# Front_LDR.net
KiCad netlist of a schematic drawn in Altium Designer
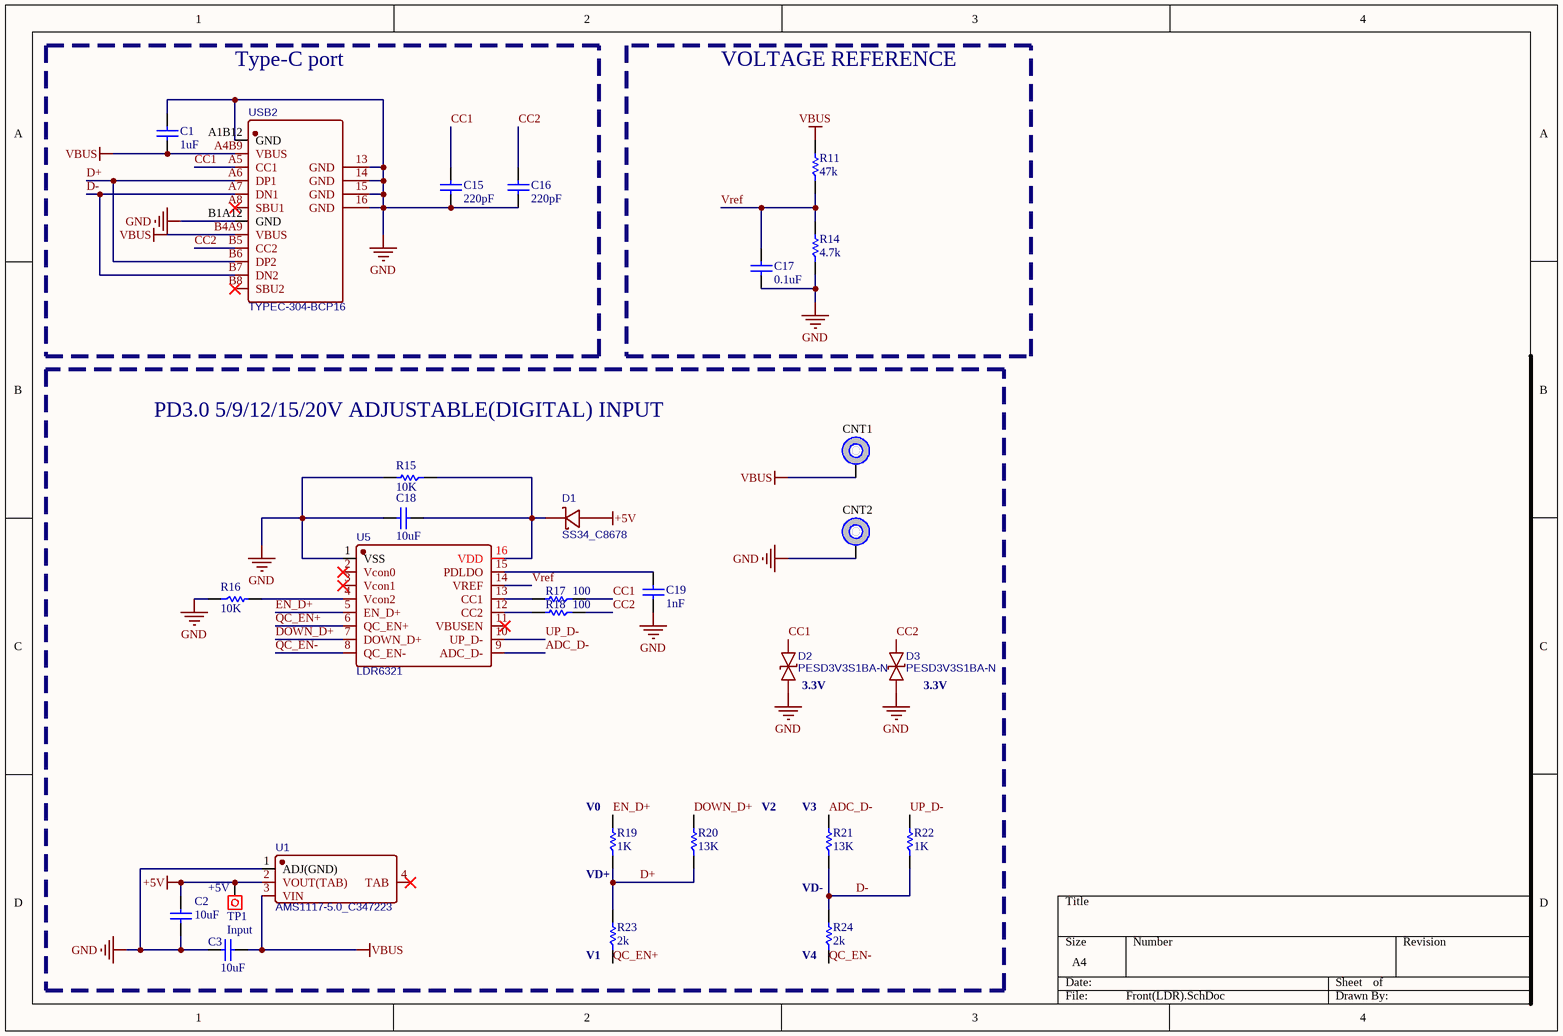
[diagram p0: Front(LDR).SchDoc]

(export (version "E")
  (design (tool "Eeschema 10.0.6"))
  (components
    (comp (ref "C1")
      (value "1uF")
      (footprint "0805C")
      (description "Capacitor")
      (fields (field (name "REVIEWED BY") "RM - 2018/08/05"))
      (libsource (lib "power supply ztc") (part "C_1uf"))
    )
    (comp (ref "C2")
      (value "10uF")
      (footprint "0805C")
      (description "Capacitor")
      (fields (field (name "REVIEWED BY") "RM - 2018/08/05"))
      (libsource (lib "Portable power supply") (part "C_10uf"))
    )
    (comp (ref "C3")
      (value "10uF")
      (footprint "0805C")
      (description "Capacitor")
      (fields (field (name "REVIEWED BY") "RM - 2018/08/05"))
      (libsource (lib "Portable power supply") (part "C_10uf"))
    )
    (comp (ref "C15")
      (value "220pF")
      (footprint "0805C")
      (description "Capacitor")
      (fields (field (name "REVIEWED BY") "RM - 2018/08/05"))
      (libsource (lib "Portable power supply") (part "C_220pF"))
    )
    (comp (ref "C16")
      (value "220pF")
      (footprint "0805C")
      (description "Capacitor")
      (fields (field (name "REVIEWED BY") "RM - 2018/08/05"))
      (libsource (lib "Portable power supply") (part "C_220pF"))
    )
    (comp (ref "C17")
      (value "0.1uF")
      (footprint "0805C")
      (description "Capacitor")
      (fields (field (name "REVIEWED BY") "RM - 2018/08/05"))
      (libsource (lib "Portable power supply") (part "C_0.1uf"))
    )
    (comp (ref "C18")
      (value "10uF")
      (footprint "0805C")
      (description "Capacitor")
      (fields (field (name "REVIEWED BY") "RM - 2018/08/05"))
      (libsource (lib "Portable power supply") (part "C_10uf"))
    )
    (comp (ref "C19")
      (value "1nF")
      (footprint "0805C")
      (description "Capacitor")
      (fields (field (name "REVIEWED BY") "RM - 2018/08/05"))
      (libsource (lib "Portable power supply") (part "C_1nf"))
    )
    (comp (ref "CNT1") (value "CST") (footprint "M3") (libsource (lib "Schlib2") (part "SO3040")))
    (comp (ref "CNT2") (value "CST") (footprint "M3") (libsource (lib "Schlib2") (part "SO3040")))
    (comp (ref "D1")
      (value "SS34_C8678")
      (footprint "DO-214AC_L4.3-W2.7-LS5.3-RD")
      (fields (field (name "BOM_MANUFACTURER PART") "SS34") (field (name "BOM_SUPPLIER PART") "C8678"))
      (libsource (lib "Portable power supply") (part "SS34_C8678"))
    )
    (comp (ref "D2")
      (value "PESD3V3S1BA-N")
      (footprint "SOD-523_L1.2-W0.8-LS1.6-BI")
      (description "TVS3V3")
      (fields (field (name "BOM_SUPPLIER PART") "C316037") (field (name "CONTRIBUTOR") "LCSC"))
      (libsource (lib "Portable power supply") (part "PESD3V3S1BA-N"))
    )
    (comp (ref "D3")
      (value "PESD3V3S1BA-N")
      (footprint "SOD-523_L1.2-W0.8-LS1.6-BI")
      (description "TVS3V3")
      (fields (field (name "BOM_SUPPLIER PART") "C316037") (field (name "CONTRIBUTOR") "LCSC"))
      (libsource (lib "Portable power supply") (part "PESD3V3S1BA-N"))
    )
    (comp (ref "R11")
      (value "47k")
      (footprint "0805")
      (description "Resistor")
      (fields (field (name "REVIEWED BY") "RM - 2018/08/05"))
      (libsource (lib "Portable power supply") (part "R_47k"))
    )
    (comp (ref "R14")
      (value "4.7k")
      (footprint "0805")
      (description "Resistor")
      (fields (field (name "REVIEWED BY") "RM - 2018/08/05"))
      (libsource (lib "Portable power supply") (part "R_4.7k"))
    )
    (comp (ref "R15")
      (value "10K")
      (footprint "0805")
      (description "Resistor")
      (fields (field (name "REVIEWED BY") "RM - 2018/08/05"))
      (libsource (lib "Portable power supply") (part "R_10k"))
    )
    (comp (ref "R16")
      (value "10K")
      (footprint "0805")
      (description "Resistor")
      (fields (field (name "REVIEWED BY") "RM - 2018/08/05"))
      (libsource (lib "Portable power supply") (part "R_10k"))
    )
    (comp (ref "R17")
      (value "100")
      (footprint "0805")
      (description "Resistor")
      (fields (field (name "REVIEWED BY") "RM - 2018/08/05"))
      (libsource (lib "Portable power supply") (part "R_100"))
    )
    (comp (ref "R18")
      (value "100")
      (footprint "0805")
      (description "Resistor")
      (fields (field (name "REVIEWED BY") "RM - 2018/08/05"))
      (libsource (lib "Portable power supply") (part "R_100"))
    )
    (comp (ref "R19")
      (value "1K")
      (footprint "0805")
      (description "Resistor")
      (fields (field (name "REVIEWED BY") "RM - 2018/08/05"))
      (libsource (lib "Portable power supply") (part "R_1k"))
    )
    (comp (ref "R20")
      (value "13K")
      (footprint "0805")
      (description "Resistor")
      (fields (field (name "REVIEWED BY") "RM - 2018/08/05"))
      (libsource (lib "Portable power supply") (part "R_13k"))
    )
    (comp (ref "R21")
      (value "13K")
      (footprint "0805")
      (description "Resistor")
      (fields (field (name "REVIEWED BY") "RM - 2018/08/05"))
      (libsource (lib "Portable power supply") (part "R_13k"))
    )
    (comp (ref "R22")
      (value "1K")
      (footprint "0805")
      (description "Resistor")
      (fields (field (name "REVIEWED BY") "RM - 2018/08/05"))
      (libsource (lib "Portable power supply") (part "R_1k"))
    )
    (comp (ref "R23")
      (value "2k")
      (footprint "0805")
      (description "Resistor")
      (fields (field (name "REVIEWED BY") "RM - 2018/08/05"))
      (libsource (lib "Portable power supply") (part "R_2k"))
    )
    (comp (ref "R24")
      (value "2k")
      (footprint "0805")
      (description "Resistor")
      (fields (field (name "REVIEWED BY") "RM - 2018/08/05"))
      (libsource (lib "Portable power supply") (part "R_2k"))
    )
    (comp (ref "TP1")
      (value "Input")
      (footprint "Testpoin")
      (description "Pad")
      (fields (field (name "Comment") "INPUT"))
      (libsource (lib "Portable power supply") (part "Test Point"))
    )
    (comp (ref "U1")
      (value "AMS1117-5.0_C347223")
      (footprint "SOT-223_L6.7-W3.5-P2.30-BR")
      (fields
        (field (name "BOM_SUPPLIER PART") "C347223")
        (field (name "BOM_MANUFACTURER PART") "AMS1117-5.0")
        (field (name "CONTRIBUTOR") "LCSC")
      )
      (libsource (lib "Portable power supply") (part "AMS1117-5.0_C347223"))
    )
    (comp (ref "U5")
      (value "LDR6321")
      (footprint "SSOP-16_L5.0-W4.4-P0.65-LS6.4-BL")
      (fields (field (name "BOM_SUPPLIER PART") "C2919632") (field (name "CONTRIBUTOR") "LCSC"))
      (libsource (lib "Portable power supply") (part "LDR6321"))
    )
    (comp (ref "USB2")
      (value "TYPEC-304-BCP16")
      (footprint "USB-C-SMD_TYPEC-304-BCP16")
      (fields (field (name "BOM_SUPPLIER PART") "C720629") (field (name "CONTRIBUTOR") "LCSC"))
      (libsource (lib "Portable power supply") (part "TYPEC-304-BCP16"))
    )
  )
  (nets
    (net (code "1") (name "+5V") (class "Default")
      (node (ref "C2") (pin "1") (pinfunction "1_1") (pintype "passive"))
      (node (ref "D1") (pin "2") (pinfunction "A_2") (pintype "passive"))
      (node (ref "TP1") (pin "1") (pintype "passive"))
      (node (ref "U1") (pin "2") (pinfunction "VOUT(TAB)_2") (pintype "passive"))
    )
    (net (code "2") (name "/ADC_D-") (class "Default")
      (node (ref "R21") (pin "2") (pintype "passive"))
      (node (ref "U5") (pin "9") (pinfunction "ADC_D-_9") (pintype "passive"))
    )
    (net (code "3") (name "/CC1") (class "Default")
      (node (ref "C15") (pin "1") (pinfunction "1_1") (pintype "passive"))
      (node (ref "D2") (pin "2") (pinfunction "2_2") (pintype "passive"))
      (node (ref "R17") (pin "1") (pintype "passive"))
      (node (ref "USB2") (pin "A5") (pinfunction "CC1_A5") (pintype "passive"))
    )
    (net (code "4") (name "/CC2") (class "Default")
      (node (ref "C16") (pin "1") (pinfunction "1_1") (pintype "passive"))
      (node (ref "D3") (pin "2") (pinfunction "2_2") (pintype "passive"))
      (node (ref "R18") (pin "1") (pintype "passive"))
      (node (ref "USB2") (pin "B5") (pinfunction "CC2_B5") (pintype "passive"))
    )
    (net (code "5") (name "/D+") (class "Default")
      (node (ref "R19") (pin "1") (pintype "passive"))
      (node (ref "R20") (pin "1") (pintype "passive"))
      (node (ref "R23") (pin "2") (pintype "passive"))
      (node (ref "USB2") (pin "A6") (pinfunction "DP1_A6") (pintype "passive"))
      (node (ref "USB2") (pin "B6") (pinfunction "DP2_B6") (pintype "passive"))
    )
    (net (code "6") (name "/D-") (class "Default")
      (node (ref "R21") (pin "1") (pintype "passive"))
      (node (ref "R22") (pin "1") (pintype "passive"))
      (node (ref "R24") (pin "2") (pintype "passive"))
      (node (ref "USB2") (pin "A7") (pinfunction "DN1_A7") (pintype "passive"))
      (node (ref "USB2") (pin "B7") (pinfunction "DN2_B7") (pintype "passive"))
    )
    (net (code "7") (name "/DOWN_D+") (class "Default")
      (node (ref "R20") (pin "2") (pintype "passive"))
      (node (ref "U5") (pin "7") (pinfunction "DOWN_D+_7") (pintype "passive"))
    )
    (net (code "8") (name "/EN_D+") (class "Default")
      (node (ref "R19") (pin "2") (pintype "passive"))
      (node (ref "U5") (pin "5") (pinfunction "EN_D+_5") (pintype "passive"))
    )
    (net (code "9") (name "/QC_EN+") (class "Default")
      (node (ref "R23") (pin "1") (pintype "passive"))
      (node (ref "U5") (pin "6") (pinfunction "QC_EN+_6") (pintype "passive"))
    )
    (net (code "10") (name "/QC_EN-") (class "Default")
      (node (ref "R24") (pin "1") (pintype "passive"))
      (node (ref "U5") (pin "8") (pinfunction "QC_EN-_8") (pintype "passive"))
    )
    (net (code "11") (name "/UP_D-") (class "Default")
      (node (ref "R22") (pin "2") (pintype "passive"))
      (node (ref "U5") (pin "10") (pinfunction "UP_D-_10") (pintype "passive"))
    )
    (net (code "12") (name "/Vref") (class "Default")
      (node (ref "C17") (pin "1") (pinfunction "1_1") (pintype "passive"))
      (node (ref "R11") (pin "1") (pintype "passive"))
      (node (ref "R14") (pin "2") (pintype "passive"))
      (node (ref "U5") (pin "14") (pinfunction "VREF_14") (pintype "passive"))
    )
    (net (code "13") (name "GND") (class "Default")
      (node (ref "C1") (pin "1") (pinfunction "1_1") (pintype "passive"))
      (node (ref "C15") (pin "2") (pinfunction "2_2") (pintype "passive"))
      (node (ref "C16") (pin "2") (pinfunction "2_2") (pintype "passive"))
      (node (ref "C17") (pin "2") (pinfunction "2_2") (pintype "passive"))
      (node (ref "C18") (pin "1") (pinfunction "1_1") (pintype "passive"))
      (node (ref "C19") (pin "2") (pinfunction "2_2") (pintype "passive"))
      (node (ref "C2") (pin "2") (pinfunction "2_2") (pintype "passive"))
      (node (ref "C3") (pin "2") (pinfunction "2_2") (pintype "passive"))
      (node (ref "CNT2") (pin "1") (pinfunction "1_1") (pintype "passive"))
      (node (ref "D2") (pin "1") (pinfunction "1_1") (pintype "passive"))
      (node (ref "D3") (pin "1") (pinfunction "1_1") (pintype "passive"))
      (node (ref "R14") (pin "1") (pintype "passive"))
      (node (ref "R15") (pin "2") (pintype "passive"))
      (node (ref "R16") (pin "1") (pintype "passive"))
      (node (ref "U1") (pin "1") (pinfunction "ADJ(GND)_1") (pintype "passive"))
      (node (ref "U5") (pin "1") (pinfunction "VSS_1") (pintype "passive"))
      (node (ref "USB2") (pin "13") (pinfunction "GND_13") (pintype "passive"))
      (node (ref "USB2") (pin "14") (pinfunction "GND_14") (pintype "passive"))
      (node (ref "USB2") (pin "15") (pinfunction "GND_15") (pintype "passive"))
      (node (ref "USB2") (pin "16") (pinfunction "GND_16") (pintype "passive"))
      (node (ref "USB2") (pin "A1B12") (pinfunction "GND_A1B12") (pintype "passive"))
      (node (ref "USB2") (pin "B1A12") (pinfunction "GND_B1A12") (pintype "passive"))
    )
    (net (code "14") (name "Net-(D1-K)") (class "Default")
      (node (ref "C18") (pin "2") (pinfunction "2_2") (pintype "passive"))
      (node (ref "D1") (pin "1") (pinfunction "K_1") (pintype "passive"))
      (node (ref "R15") (pin "1") (pintype "passive"))
      (node (ref "U5") (pin "16") (pinfunction "VDD_16") (pintype "passive"))
    )
    (net (code "15") (name "Net-(U5-CC1)") (class "Default")
      (node (ref "R17") (pin "2") (pintype "passive"))
      (node (ref "U5") (pin "13") (pinfunction "CC1_13") (pintype "passive"))
    )
    (net (code "16") (name "Net-(U5-CC2)") (class "Default")
      (node (ref "R18") (pin "2") (pintype "passive"))
      (node (ref "U5") (pin "12") (pinfunction "CC2_12") (pintype "passive"))
    )
    (net (code "17") (name "Net-(U5-PDLDO)") (class "Default")
      (node (ref "C19") (pin "1") (pinfunction "1_1") (pintype "passive"))
      (node (ref "U5") (pin "15") (pinfunction "PDLDO_15") (pintype "passive"))
    )
    (net (code "18") (name "Net-(U5-Vcon2)") (class "Default")
      (node (ref "R16") (pin "2") (pintype "passive"))
      (node (ref "U5") (pin "4") (pinfunction "Vcon2_4") (pintype "passive"))
    )
    (net (code "19") (name "VBUS") (class "Default")
      (node (ref "C1") (pin "2") (pinfunction "2_2") (pintype "passive"))
      (node (ref "C3") (pin "1") (pinfunction "1_1") (pintype "passive"))
      (node (ref "CNT1") (pin "1") (pinfunction "1_1") (pintype "passive"))
      (node (ref "R11") (pin "2") (pintype "passive"))
      (node (ref "U1") (pin "3") (pinfunction "VIN_3") (pintype "passive"))
      (node (ref "USB2") (pin "A4B9") (pinfunction "VBUS_A4B9") (pintype "passive"))
      (node (ref "USB2") (pin "B4A9") (pinfunction "VBUS_B4A9") (pintype "passive"))
    )
    (net (code "20") (name "unconnected-(CNT1-Pad1)") (class "Default")
      (node (ref "CNT1") (pin "1") (pinfunction "1_1") (pintype "passive"))
    )
    (net (code "21") (name "unconnected-(CNT1-Pad1)_1") (class "Default")
      (node (ref "CNT1") (pin "1") (pinfunction "1_1") (pintype "passive"))
    )
    (net (code "22") (name "unconnected-(CNT1-Pad1)_2") (class "Default")
      (node (ref "CNT1") (pin "1") (pinfunction "1_1") (pintype "passive"))
    )
    (net (code "23") (name "unconnected-(CNT2-Pad1)") (class "Default")
      (node (ref "CNT2") (pin "1") (pinfunction "1_1") (pintype "passive"))
    )
    (net (code "24") (name "unconnected-(CNT2-Pad1)_1") (class "Default")
      (node (ref "CNT2") (pin "1") (pinfunction "1_1") (pintype "passive"))
    )
    (net (code "25") (name "unconnected-(CNT2-Pad1)_2") (class "Default")
      (node (ref "CNT2") (pin "1") (pinfunction "1_1") (pintype "passive"))
    )
    (net (code "26") (name "unconnected-(U1-TAB-Pad4)") (class "Default")
      (node (ref "U1") (pin "4") (pinfunction "TAB_4") (pintype "passive+no_connect"))
    )
    (net (code "27") (name "unconnected-(U5-VBUSEN-Pad11)") (class "Default")
      (node (ref "U5") (pin "11") (pinfunction "VBUSEN_11") (pintype "passive+no_connect"))
    )
    (net (code "28") (name "unconnected-(U5-Vcon0-Pad2)") (class "Default")
      (node (ref "U5") (pin "2") (pinfunction "Vcon0_2") (pintype "passive+no_connect"))
    )
    (net (code "29") (name "unconnected-(U5-Vcon1-Pad3)") (class "Default")
      (node (ref "U5") (pin "3") (pinfunction "Vcon1_3") (pintype "passive+no_connect"))
    )
    (net (code "30") (name "unconnected-(USB2-SBU1-PadA8)") (class "Default")
      (node (ref "USB2") (pin "A8") (pinfunction "SBU1_A8") (pintype "passive+no_connect"))
    )
    (net (code "31") (name "unconnected-(USB2-SBU2-PadB8)") (class "Default")
      (node (ref "USB2") (pin "B8") (pinfunction "SBU2_B8") (pintype "passive+no_connect"))
    )
  )
)
